# SCHMITT_LED.net
KiCad netlist of a schematic drawn in Altium Designer
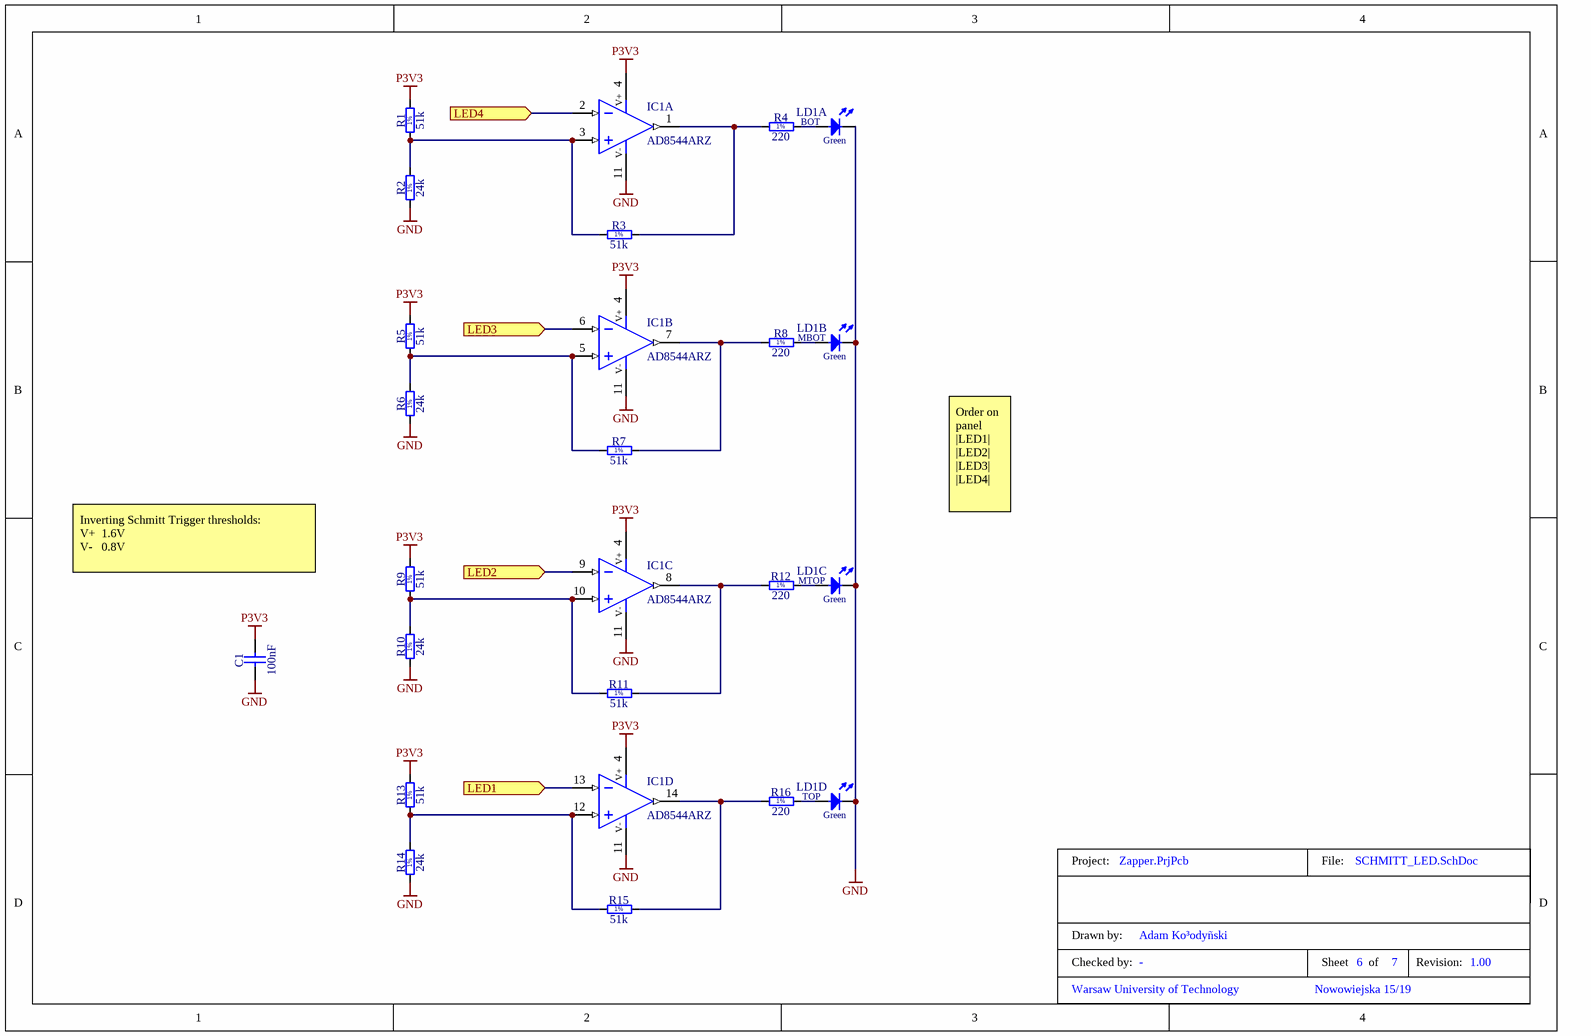
[diagram p0: SCHMITT_LED.SchDoc]

(export (version "E")
  (design (tool "Eeschema 10.0.6"))
  (components
    (comp (ref "C1")
      (value "100nF")
      (footprint "CAPC1005X55N")
      (description "Non-polarised capacitor")
      (fields
        (field (name "PART NUMBER") "CC0402_100NF_16V_10%_X7R")
        (field (name "VOLTAGE") "16V")
        (field (name "AUTHOR") "CERN DEM JLC")
      )
      (libsource (lib "Capacitors") (part "Capacitor - non polarized"))
    )
    (comp (ref "IC1")
      (value "AD8544ARZ")
      (footprint "SOIC127P600X175-14N")
      (description "Quad Operational Amplifier")
      (fields (field (name "MANUFACTURER") "ANALOG DEVICES") (field (name "AUTHOR") "CERN DEM JLC"))
      (libsource (lib "ICs And Semiconductors") (part "Operational Amplifier x4 Type1"))
    )
    (comp (ref "LD1")
      (value "Green")
      (footprint "LED_BIVAR_H485CGDL")
      (description "LED x4 Green 1C2A-BOT_3C4A_5C6A_7C8A-TOP")
      (fields
        (field (name "PART NUMBER") "LED_BIVAR_H485CGDL")
        (field (name "MANUFACTURER") "BIVAR")
        (field (name "AUTHOR") "CERN DEM JLC")
      )
      (libsource (lib "ICs And Semiconductors") (part "LED x4 Green 1C2A-BOT_3C4A_5C6A_7C8A-TOP"))
    )
    (comp (ref "R1")
      (value "51k")
      (footprint "RESC1608X55N")
      (description "Resistor - 1%")
      (fields
        (field (name "PART NUMBER") "R0603_51K_1%_0.1W_100PPM")
        (field (name "POWER") "0.1W")
        (field (name "AUTHOR") "CERN DEM JLC")
      )
      (libsource (lib "Resistors") (part "Resistor - 1%"))
    )
    (comp (ref "R2")
      (value "24k")
      (footprint "RESC1608X55N")
      (description "Resistor - 1%")
      (fields
        (field (name "PART NUMBER") "R0603_24K_1%_0.1W_100PPM")
        (field (name "POWER") "0.1W")
        (field (name "AUTHOR") "CERN DEM JLC")
      )
      (libsource (lib "Resistors") (part "Resistor - 1%"))
    )
    (comp (ref "R3")
      (value "51k")
      (footprint "RESC1608X55N")
      (description "Resistor - 1%")
      (fields
        (field (name "PART NUMBER") "R0603_51K_1%_0.1W_100PPM")
        (field (name "POWER") "0.1W")
        (field (name "AUTHOR") "CERN DEM JLC")
      )
      (libsource (lib "Resistors") (part "Resistor - 1%"))
    )
    (comp (ref "R4")
      (value "220")
      (footprint "RESC1608X55N")
      (description "Resistor - 1%")
      (fields
        (field (name "PART NUMBER") "R0603_220R_1%_0.1W_100PPM")
        (field (name "POWER") "0.1W")
        (field (name "AUTHOR") "CERN DEM JLC")
      )
      (libsource (lib "Resistors") (part "Resistor - 1%"))
    )
    (comp (ref "R5")
      (value "51k")
      (footprint "RESC1608X55N")
      (description "Resistor - 1%")
      (fields
        (field (name "PART NUMBER") "R0603_51K_1%_0.1W_100PPM")
        (field (name "POWER") "0.1W")
        (field (name "AUTHOR") "CERN DEM JLC")
      )
      (libsource (lib "Resistors") (part "Resistor - 1%"))
    )
    (comp (ref "R6")
      (value "24k")
      (footprint "RESC1608X55N")
      (description "Resistor - 1%")
      (fields
        (field (name "PART NUMBER") "R0603_24K_1%_0.1W_100PPM")
        (field (name "POWER") "0.1W")
        (field (name "AUTHOR") "CERN DEM JLC")
      )
      (libsource (lib "Resistors") (part "Resistor - 1%"))
    )
    (comp (ref "R7")
      (value "51k")
      (footprint "RESC1608X55N")
      (description "Resistor - 1%")
      (fields
        (field (name "PART NUMBER") "R0603_51K_1%_0.1W_100PPM")
        (field (name "POWER") "0.1W")
        (field (name "AUTHOR") "CERN DEM JLC")
      )
      (libsource (lib "Resistors") (part "Resistor - 1%"))
    )
    (comp (ref "R8")
      (value "220")
      (footprint "RESC1608X55N")
      (description "Resistor - 1%")
      (fields
        (field (name "PART NUMBER") "R0603_220R_1%_0.1W_100PPM")
        (field (name "POWER") "0.1W")
        (field (name "AUTHOR") "CERN DEM JLC")
      )
      (libsource (lib "Resistors") (part "Resistor - 1%"))
    )
    (comp (ref "R9")
      (value "51k")
      (footprint "RESC1608X55N")
      (description "Resistor - 1%")
      (fields
        (field (name "PART NUMBER") "R0603_51K_1%_0.1W_100PPM")
        (field (name "POWER") "0.1W")
        (field (name "AUTHOR") "CERN DEM JLC")
      )
      (libsource (lib "Resistors") (part "Resistor - 1%"))
    )
    (comp (ref "R10")
      (value "24k")
      (footprint "RESC1608X55N")
      (description "Resistor - 1%")
      (fields
        (field (name "PART NUMBER") "R0603_24K_1%_0.1W_100PPM")
        (field (name "POWER") "0.1W")
        (field (name "AUTHOR") "CERN DEM JLC")
      )
      (libsource (lib "Resistors") (part "Resistor - 1%"))
    )
    (comp (ref "R11")
      (value "51k")
      (footprint "RESC1608X55N")
      (description "Resistor - 1%")
      (fields
        (field (name "PART NUMBER") "R0603_51K_1%_0.1W_100PPM")
        (field (name "POWER") "0.1W")
        (field (name "AUTHOR") "CERN DEM JLC")
      )
      (libsource (lib "Resistors") (part "Resistor - 1%"))
    )
    (comp (ref "R12")
      (value "220")
      (footprint "RESC1608X55N")
      (description "Resistor - 1%")
      (fields
        (field (name "PART NUMBER") "R0603_220R_1%_0.1W_100PPM")
        (field (name "POWER") "0.1W")
        (field (name "AUTHOR") "CERN DEM JLC")
      )
      (libsource (lib "Resistors") (part "Resistor - 1%"))
    )
    (comp (ref "R13")
      (value "51k")
      (footprint "RESC1608X55N")
      (description "Resistor - 1%")
      (fields
        (field (name "PART NUMBER") "R0603_51K_1%_0.1W_100PPM")
        (field (name "POWER") "0.1W")
        (field (name "AUTHOR") "CERN DEM JLC")
      )
      (libsource (lib "Resistors") (part "Resistor - 1%"))
    )
    (comp (ref "R14")
      (value "24k")
      (footprint "RESC1608X55N")
      (description "Resistor - 1%")
      (fields
        (field (name "PART NUMBER") "R0603_24K_1%_0.1W_100PPM")
        (field (name "POWER") "0.1W")
        (field (name "AUTHOR") "CERN DEM JLC")
      )
      (libsource (lib "Resistors") (part "Resistor - 1%"))
    )
    (comp (ref "R15")
      (value "51k")
      (footprint "RESC1608X55N")
      (description "Resistor - 1%")
      (fields
        (field (name "PART NUMBER") "R0603_51K_1%_0.1W_100PPM")
        (field (name "POWER") "0.1W")
        (field (name "AUTHOR") "CERN DEM JLC")
      )
      (libsource (lib "Resistors") (part "Resistor - 1%"))
    )
    (comp (ref "R16")
      (value "220")
      (footprint "RESC1608X55N")
      (description "Resistor - 1%")
      (fields
        (field (name "PART NUMBER") "R0603_220R_1%_0.1W_100PPM")
        (field (name "POWER") "0.1W")
        (field (name "AUTHOR") "CERN DEM JLC")
      )
      (libsource (lib "Resistors") (part "Resistor - 1%"))
    )
    (comp (ref "TitleBlock6") (value "TitleBlock") (libsource (lib "InzLib") (part "TitleBlock")))
  )
  (nets
    (net (code "1") (name "/LED1") (class "Default")
      (node (ref "IC1") (pin "13") (pinfunction "IN-_13") (pintype "input"))
    )
    (net (code "2") (name "/LED2") (class "Default")
      (node (ref "IC1") (pin "9") (pinfunction "IN-_9") (pintype "input"))
    )
    (net (code "3") (name "/LED3") (class "Default")
      (node (ref "IC1") (pin "6") (pinfunction "IN-_6") (pintype "input"))
    )
    (net (code "4") (name "/LED4") (class "Default")
      (node (ref "IC1") (pin "2") (pinfunction "IN-_2") (pintype "input"))
    )
    (net (code "5") (name "GND") (class "Default")
      (node (ref "C1") (pin "1") (pinfunction "1_1") (pintype "passive"))
      (node (ref "IC1") (pin "11") (pinfunction "V-_11") (pintype "power_in"))
      (node (ref "LD1") (pin "1") (pinfunction "C_1") (pintype "passive"))
      (node (ref "LD1") (pin "3") (pinfunction "C_3") (pintype "passive"))
      (node (ref "LD1") (pin "5") (pinfunction "C_5") (pintype "passive"))
      (node (ref "LD1") (pin "7") (pinfunction "C_7") (pintype "passive"))
      (node (ref "R10") (pin "1") (pinfunction "1_1") (pintype "passive"))
      (node (ref "R14") (pin "1") (pinfunction "1_1") (pintype "passive"))
      (node (ref "R2") (pin "1") (pinfunction "1_1") (pintype "passive"))
      (node (ref "R6") (pin "1") (pinfunction "1_1") (pintype "passive"))
    )
    (net (code "6") (name "Net-(IC1A-IN+)") (class "Default")
      (node (ref "IC1") (pin "3") (pinfunction "IN+_3") (pintype "input"))
      (node (ref "R1") (pin "1") (pinfunction "1_1") (pintype "passive"))
      (node (ref "R2") (pin "2") (pinfunction "2_2") (pintype "passive"))
      (node (ref "R3") (pin "1") (pinfunction "1_1") (pintype "passive"))
    )
    (net (code "7") (name "Net-(IC1A-OUT)") (class "Default")
      (node (ref "IC1") (pin "1") (pinfunction "OUT_1") (pintype "output"))
      (node (ref "R3") (pin "2") (pinfunction "2_2") (pintype "passive"))
      (node (ref "R4") (pin "1") (pinfunction "1_1") (pintype "passive"))
    )
    (net (code "8") (name "Net-(IC1B-IN+)") (class "Default")
      (node (ref "IC1") (pin "5") (pinfunction "IN+_5") (pintype "input"))
      (node (ref "R5") (pin "1") (pinfunction "1_1") (pintype "passive"))
      (node (ref "R6") (pin "2") (pinfunction "2_2") (pintype "passive"))
      (node (ref "R7") (pin "1") (pinfunction "1_1") (pintype "passive"))
    )
    (net (code "9") (name "Net-(IC1B-OUT)") (class "Default")
      (node (ref "IC1") (pin "7") (pinfunction "OUT_7") (pintype "output"))
      (node (ref "R7") (pin "2") (pinfunction "2_2") (pintype "passive"))
      (node (ref "R8") (pin "1") (pinfunction "1_1") (pintype "passive"))
    )
    (net (code "10") (name "Net-(IC1C-IN+)") (class "Default")
      (node (ref "IC1") (pin "10") (pinfunction "IN+_10") (pintype "input"))
      (node (ref "R10") (pin "2") (pinfunction "2_2") (pintype "passive"))
      (node (ref "R11") (pin "1") (pinfunction "1_1") (pintype "passive"))
      (node (ref "R9") (pin "1") (pinfunction "1_1") (pintype "passive"))
    )
    (net (code "11") (name "Net-(IC1C-OUT)") (class "Default")
      (node (ref "IC1") (pin "8") (pinfunction "OUT_8") (pintype "output"))
      (node (ref "R11") (pin "2") (pinfunction "2_2") (pintype "passive"))
      (node (ref "R12") (pin "1") (pinfunction "1_1") (pintype "passive"))
    )
    (net (code "12") (name "Net-(IC1D-IN+)") (class "Default")
      (node (ref "IC1") (pin "12") (pinfunction "IN+_12") (pintype "input"))
      (node (ref "R13") (pin "1") (pinfunction "1_1") (pintype "passive"))
      (node (ref "R14") (pin "2") (pinfunction "2_2") (pintype "passive"))
      (node (ref "R15") (pin "1") (pinfunction "1_1") (pintype "passive"))
    )
    (net (code "13") (name "Net-(IC1D-OUT)") (class "Default")
      (node (ref "IC1") (pin "14") (pinfunction "OUT_14") (pintype "output"))
      (node (ref "R15") (pin "2") (pinfunction "2_2") (pintype "passive"))
      (node (ref "R16") (pin "1") (pinfunction "1_1") (pintype "passive"))
    )
    (net (code "14") (name "Net-(LD1A-A)") (class "Default")
      (node (ref "LD1") (pin "2") (pinfunction "A_2") (pintype "passive"))
      (node (ref "R4") (pin "2") (pinfunction "2_2") (pintype "passive"))
    )
    (net (code "15") (name "Net-(LD1B-A)") (class "Default")
      (node (ref "LD1") (pin "4") (pinfunction "A_4") (pintype "passive"))
      (node (ref "R8") (pin "2") (pinfunction "2_2") (pintype "passive"))
    )
    (net (code "16") (name "Net-(LD1C-A)") (class "Default")
      (node (ref "LD1") (pin "6") (pinfunction "A_6") (pintype "passive"))
      (node (ref "R12") (pin "2") (pinfunction "2_2") (pintype "passive"))
    )
    (net (code "17") (name "Net-(LD1D-A)") (class "Default")
      (node (ref "LD1") (pin "8") (pinfunction "A_8") (pintype "passive"))
      (node (ref "R16") (pin "2") (pinfunction "2_2") (pintype "passive"))
    )
    (net (code "18") (name "P3V3") (class "Default")
      (node (ref "C1") (pin "2") (pinfunction "2_2") (pintype "passive"))
      (node (ref "IC1") (pin "4") (pinfunction "V+_4") (pintype "power_in"))
      (node (ref "R1") (pin "2") (pinfunction "2_2") (pintype "passive"))
      (node (ref "R13") (pin "2") (pinfunction "2_2") (pintype "passive"))
      (node (ref "R5") (pin "2") (pinfunction "2_2") (pintype "passive"))
      (node (ref "R9") (pin "2") (pinfunction "2_2") (pintype "passive"))
    )
  )
)
